# Vertap_Connectors.net
KiCad netlist of a schematic drawn in Altium Designer
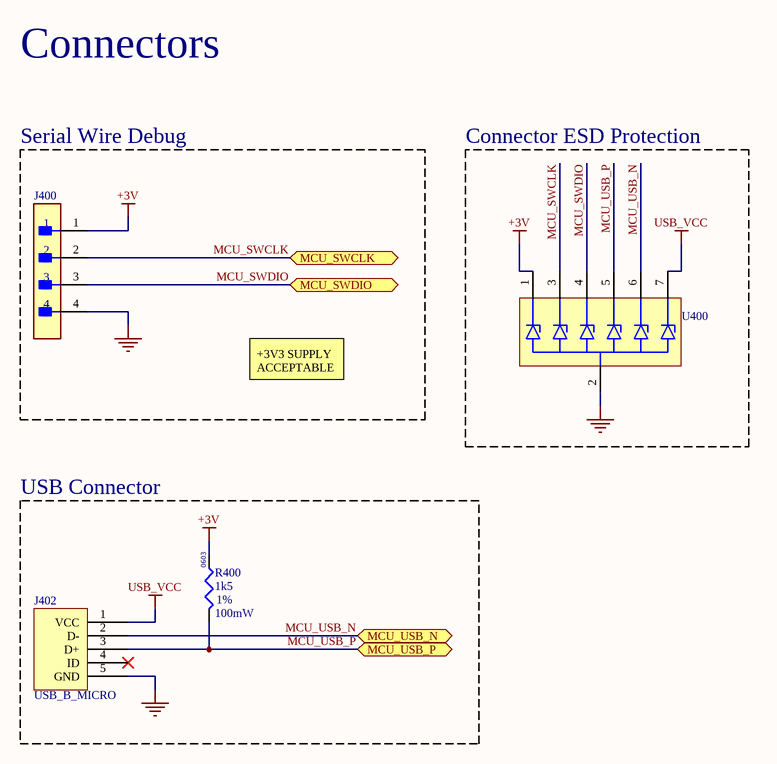
[diagram p0: Vertap_Connectors.SchDoc]

(export (version "E")
  (design (tool "Eeschema 10.0.6"))
  (components
    (comp (ref "J400")
      (value "GEC04SBSN-M89")
      (footprint "FP-GEC04SBSN-M89-MFG")
      (description "CONN HEADER SMD R/A 4POS 2.54MM")
      (libsource (lib "Altium Content Vault") (part "299a8cea1bdcbc3624fe62c390fa72c"))
    )
    (comp (ref "J402")
      (value "USB_B_MICRO")
      (footprint "MUSB-B5-S-RA-SMT-PP-T/R")
      (description "MINI USB, TYPE B, RIGHT ANGLE, S")
      (libsource (lib "Vertap_SchLib") (part "MUSB-B5-S-RA-SMT-PP-T/R"))
    )
    (comp (ref "R400")
      (value "1k5")
      (footprint "RES_0603_YAGEO")
      (description "RES 1.5K OHM 1% 1/10W 0603")
      (fields
        (field (name "MANUFACTURER") "YAGEO")
        (field (name "MANUFACTURER PART NUMBER") "RC0603FR-131K5L")
      )
      (libsource (lib "Vertap_SchLib") (part "RES_0603_1.5K"))
    )
    (comp (ref "U400")
      (value "PUSB3FR6Z")
      (footprint "PUSB3FR6Z")
      (description "TVS DIODE 3.3VWM 3VC 7XSON")
      (libsource (lib "Vertap_SchLib") (part "PUSB3FR6Z"))
    )
  )
  (nets
    (net (code "1") (name "+3V") (class "Default")
      (node (ref "J400") (pin "1") (pinfunction "1_1") (pintype "passive"))
      (node (ref "R400") (pin "1") (pinfunction "1_1") (pintype "passive"))
      (node (ref "U400") (pin "1") (pinfunction "1_1") (pintype "passive"))
    )
    (net (code "2") (name "/MCU_SWCLK") (class "Default")
      (node (ref "J400") (pin "2") (pinfunction "2_2") (pintype "passive"))
      (node (ref "U400") (pin "3") (pinfunction "3_3") (pintype "passive"))
    )
    (net (code "3") (name "/MCU_SWDIO") (class "Default")
      (node (ref "J400") (pin "3") (pinfunction "3_3") (pintype "passive"))
      (node (ref "U400") (pin "4") (pinfunction "4_4") (pintype "passive"))
    )
    (net (code "4") (name "/MCU_USB_N") (class "Default")
      (node (ref "J402") (pin "2") (pinfunction "D-_2") (pintype "passive"))
      (node (ref "U400") (pin "6") (pinfunction "6_6") (pintype "passive"))
    )
    (net (code "5") (name "/MCU_USB_P") (class "Default")
      (node (ref "J402") (pin "3") (pinfunction "D+_3") (pintype "passive"))
      (node (ref "R400") (pin "2") (pinfunction "2_2") (pintype "passive"))
      (node (ref "U400") (pin "5") (pinfunction "5_5") (pintype "passive"))
    )
    (net (code "6") (name "GND") (class "Default")
      (node (ref "J400") (pin "4") (pinfunction "4_4") (pintype "passive"))
      (node (ref "J402") (pin "5") (pinfunction "GND_5") (pintype "passive"))
      (node (ref "U400") (pin "2") (pinfunction "GND_2") (pintype "passive"))
    )
    (net (code "7") (name "USB_VCC") (class "Default")
      (node (ref "J402") (pin "1") (pinfunction "VCC_1") (pintype "passive"))
      (node (ref "U400") (pin "7") (pinfunction "7_7") (pintype "passive"))
    )
    (net (code "8") (name "unconnected-(J402-ID-Pad4)") (class "Default")
      (node (ref "J402") (pin "4") (pinfunction "ID_4") (pintype "passive+no_connect"))
    )
  )
)
